# tvout.net
KiCad netlist of a schematic drawn in EAGLE
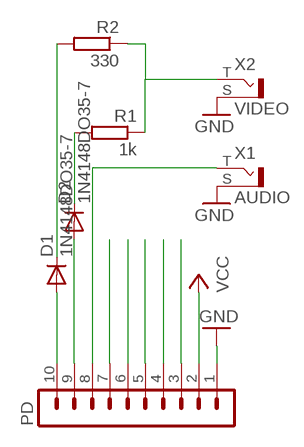
[diagram p0: schematic, sheet 1]

(export (version "E")
  (design (tool "Eeschema 10.0.6"))
  (components
    (comp (ref "D1")
      (value "1N4148DO35-7")
      (footprint "eagle-import:DO35-7")
      (libsource (lib "eagle-import") (part "1N4148DO35-7"))
    )
    (comp (ref "D2")
      (value "1N4148DO35-7")
      (footprint "eagle-import:DO35-7")
      (libsource (lib "eagle-import") (part "1N4148DO35-7"))
    )
    (comp (ref "PD")
      (value "MA10-1W")
      (footprint "eagle-import:MA10-1W")
      (libsource (lib "eagle-import") (part "MA10-1W"))
    )
    (comp (ref "R1")
      (value "1k")
      (footprint "eagle-import:0207_10")
      (libsource (lib "eagle-import") (part "R-EU_0207/10"))
    )
    (comp (ref "R2")
      (value "330")
      (footprint "eagle-import:0207_12")
      (libsource (lib "eagle-import") (part "R-EU_0207/12"))
    )
    (comp (ref "X1")
      (value "AUDIO")
      (footprint "eagle-import:WBTOR1")
      (fields (field (name "MPN") "WBTOR 1 BLACK"))
      (libsource (lib "eagle-import") (part "WBTOR1"))
    )
    (comp (ref "X2")
      (value "VIDEO")
      (footprint "eagle-import:WBTOR1")
      (fields (field (name "MPN") "WBTOR 1 BLACK"))
      (libsource (lib "eagle-import") (part "WBTOR1"))
    )
  )
  (nets
    (net (code "1") (name "GND") (class "Default")
      (node (ref "PD") (pin "1") (pinfunction "1_1") (pintype "passive"))
      (node (ref "X1") (pin "S") (pinfunction "S_S") (pintype "passive"))
      (node (ref "X2") (pin "S") (pinfunction "S_S") (pintype "passive"))
    )
    (net (code "2") (name "Net-(D1-PadA)") (class "Default")
      (node (ref "D1") (pin "A") (pinfunction "A_A") (pintype "passive"))
      (node (ref "PD") (pin "10") (pinfunction "10_10") (pintype "passive"))
    )
    (net (code "3") (name "Net-(D1-PadC)") (class "Default")
      (node (ref "D1") (pin "C") (pinfunction "C_C") (pintype "passive"))
      (node (ref "R2") (pin "2") (pinfunction "2_2") (pintype "passive"))
    )
    (net (code "4") (name "Net-(D2-PadA)") (class "Default")
      (node (ref "D2") (pin "A") (pinfunction "A_A") (pintype "passive"))
      (node (ref "PD") (pin "9") (pinfunction "9_9") (pintype "passive"))
    )
    (net (code "5") (name "Net-(D2-PadC)") (class "Default")
      (node (ref "D2") (pin "C") (pinfunction "C_C") (pintype "passive"))
      (node (ref "R1") (pin "2") (pinfunction "2_2") (pintype "passive"))
    )
    (net (code "6") (name "Net-(PD-Pad8)") (class "Default")
      (node (ref "PD") (pin "8") (pinfunction "8_8") (pintype "passive"))
      (node (ref "X1") (pin "T") (pinfunction "T_T") (pintype "passive"))
    )
    (net (code "7") (name "Net-(R1-Pad1)") (class "Default")
      (node (ref "R1") (pin "1") (pinfunction "1_1") (pintype "passive"))
      (node (ref "R2") (pin "1") (pinfunction "1_1") (pintype "passive"))
      (node (ref "X2") (pin "T") (pinfunction "T_T") (pintype "passive"))
    )
    (net (code "8") (name "VCC") (class "Default")
      (node (ref "PD") (pin "2") (pinfunction "2_2") (pintype "passive"))
    )
    (net (code "9") (name "unconnected-(PD-Pad3)") (class "Default")
      (node (ref "PD") (pin "3") (pinfunction "3_3") (pintype "passive"))
    )
    (net (code "10") (name "unconnected-(PD-Pad4)") (class "Default")
      (node (ref "PD") (pin "4") (pinfunction "4_4") (pintype "passive"))
    )
    (net (code "11") (name "unconnected-(PD-Pad5)") (class "Default")
      (node (ref "PD") (pin "5") (pinfunction "5_5") (pintype "passive"))
    )
    (net (code "12") (name "unconnected-(PD-Pad6)") (class "Default")
      (node (ref "PD") (pin "6") (pinfunction "6_6") (pintype "passive"))
    )
    (net (code "13") (name "unconnected-(PD-Pad7)") (class "Default")
      (node (ref "PD") (pin "7") (pinfunction "7_7") (pintype "passive"))
    )
  )
)
